# 1_P1_schdoc.net
KiCad netlist of a schematic drawn in Altium Designer
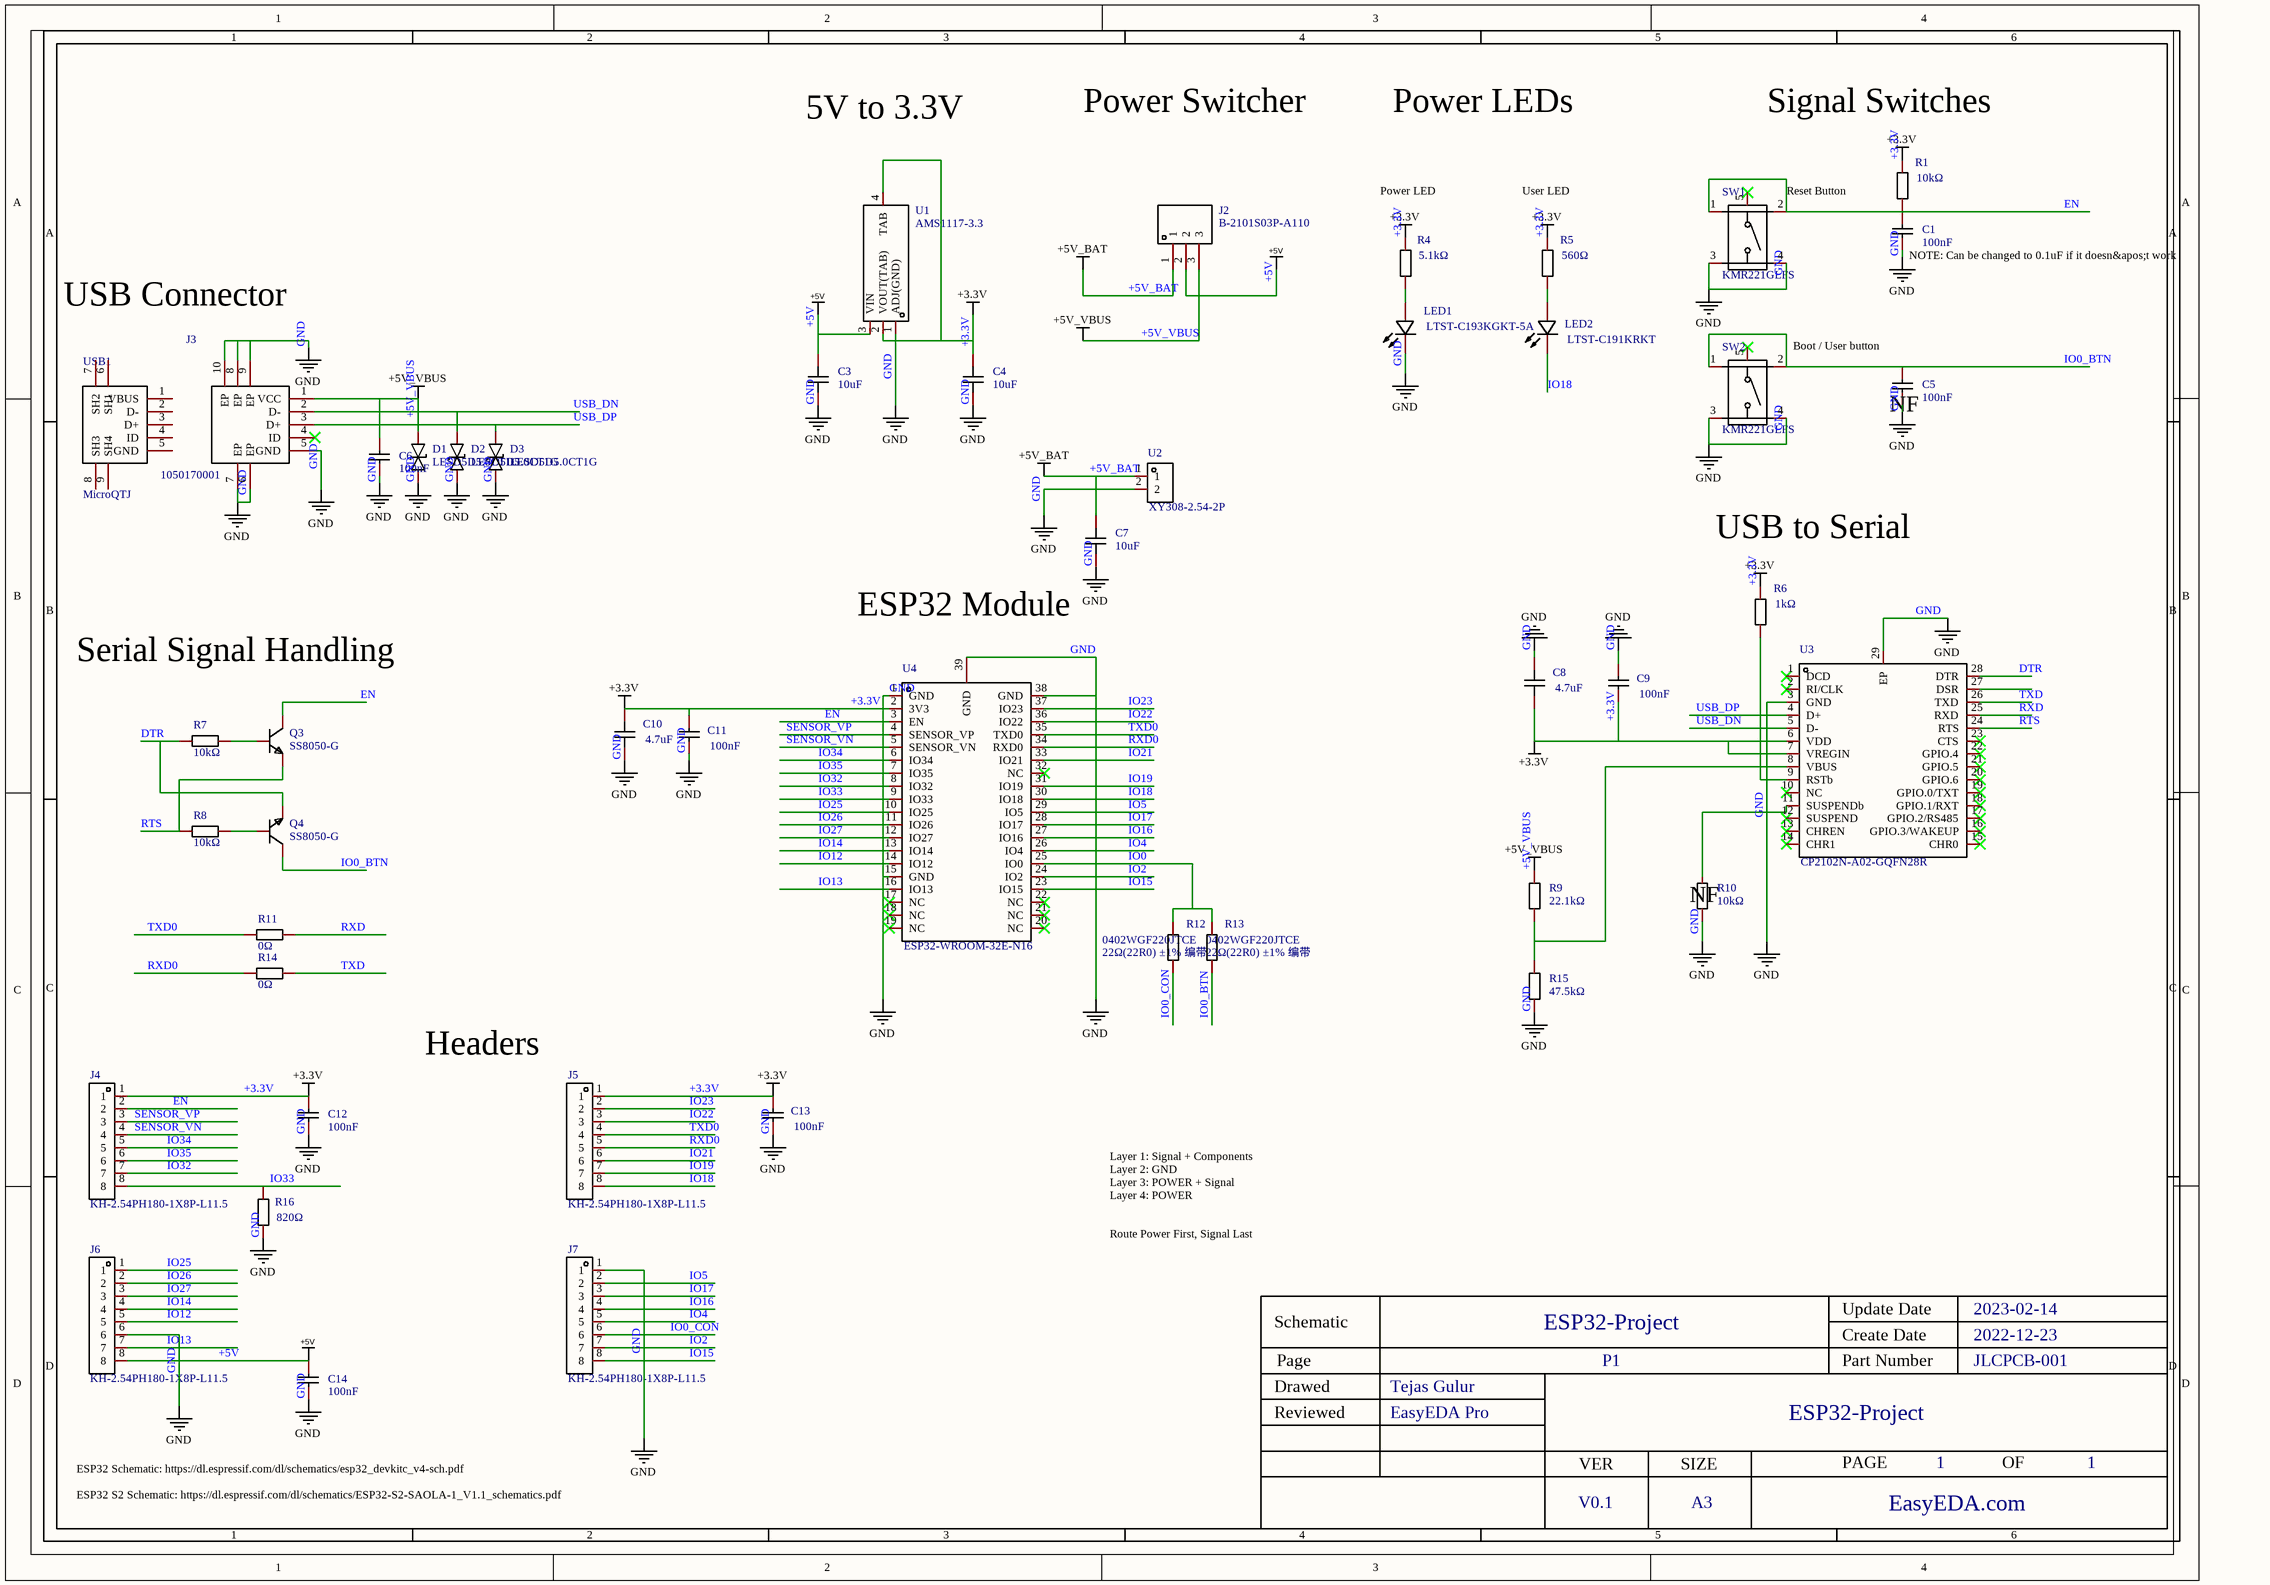
[diagram p0: 1_P1.schdoc.schdoc]

(export (version "E")
  (design (tool "Eeschema 10.0.6"))
  (components
    (comp (ref "C1")
      (value "100nF")
      (fields
        (field (name "NAME") "100nF")
        (field (name "MANUFACTURER") "SAMSUNG(三星)")
        (field (name "MANUFACTURER PART") "CL05B104KO5NNNC")
        (field (name "TOLERANCE") "±10%")
      )
      (libsource (lib "altium-import") (part "root_1_CL05B104KO5NNNC_"))
    )
    (comp (ref "C3")
      (value "10uF")
      (fields
        (field (name "NAME") "10uF")
        (field (name "MANUFACTURER") "SAMSUNG(三星)")
        (field (name "MANUFACTURER PART") "CL05A106MP5NUNC")
        (field (name "TOLERANCE") "±20%")
      )
      (libsource (lib "altium-import") (part "root_1_CL05A106MP5NUNC_C315248_"))
    )
    (comp (ref "C4")
      (value "10uF")
      (fields
        (field (name "NAME") "10uF")
        (field (name "MANUFACTURER") "SAMSUNG(三星)")
        (field (name "MANUFACTURER PART") "CL05A106MP5NUNC")
        (field (name "TOLERANCE") "±20%")
      )
      (libsource (lib "altium-import") (part "root_1_CL05A106MP5NUNC_C315248_"))
    )
    (comp (ref "C5")
      (value "100nF")
      (fields
        (field (name "NAME") "100nF")
        (field (name "MANUFACTURER") "SAMSUNG(三星)")
        (field (name "MANUFACTURER PART") "CL05B104KO5NNNC")
        (field (name "TOLERANCE") "±10%")
      )
      (libsource (lib "altium-import") (part "root_1_CL05B104KO5NNNC_"))
    )
    (comp (ref "C6")
      (value "100nF")
      (fields
        (field (name "NAME") "100nF")
        (field (name "MANUFACTURER") "SAMSUNG(三星)")
        (field (name "MANUFACTURER PART") "CL05B104KO5NNNC")
        (field (name "TOLERANCE") "±10%")
      )
      (libsource (lib "altium-import") (part "root_1_CL05B104KO5NNNC_"))
    )
    (comp (ref "C7")
      (value "10uF")
      (fields
        (field (name "NAME") "10uF")
        (field (name "MANUFACTURER") "SAMSUNG(三星)")
        (field (name "MANUFACTURER PART") "CL05A106MP5NUNC")
        (field (name "TOLERANCE") "±20%")
      )
      (libsource (lib "altium-import") (part "root_1_CL05A106MP5NUNC_C315248_"))
    )
    (comp (ref "C8")
      (value "4.7uF")
      (fields
        (field (name "NAME") "4.7uF")
        (field (name "MANUFACTURER") "SAMSUNG(三星)")
        (field (name "MANUFACTURER PART") "CL05A475KP5NRNC")
        (field (name "TOLERANCE") "±10%")
      )
      (libsource (lib "altium-import") (part "root_0_CL05A475KP5NRNC_"))
    )
    (comp (ref "C9")
      (value "100nF")
      (fields
        (field (name "NAME") "100nF")
        (field (name "MANUFACTURER") "SAMSUNG(三星)")
        (field (name "MANUFACTURER PART") "CL05B104KO5NNNC")
        (field (name "TOLERANCE") "±10%")
      )
      (libsource (lib "altium-import") (part "root_1_CL05B104KO5NNNC_"))
    )
    (comp (ref "C10")
      (value "4.7uF")
      (fields
        (field (name "NAME") "4.7uF")
        (field (name "MANUFACTURER") "SAMSUNG(三星)")
        (field (name "MANUFACTURER PART") "CL05A475KP5NRNC")
        (field (name "TOLERANCE") "±10%")
      )
      (libsource (lib "altium-import") (part "root_0_CL05A475KP5NRNC_"))
    )
    (comp (ref "C11")
      (value "100nF")
      (fields
        (field (name "NAME") "100nF")
        (field (name "MANUFACTURER") "SAMSUNG(三星)")
        (field (name "MANUFACTURER PART") "CL05B104KO5NNNC")
        (field (name "TOLERANCE") "±10%")
      )
      (libsource (lib "altium-import") (part "root_1_CL05B104KO5NNNC_"))
    )
    (comp (ref "C12")
      (value "100nF")
      (fields
        (field (name "NAME") "100nF")
        (field (name "MANUFACTURER") "SAMSUNG(三星)")
        (field (name "MANUFACTURER PART") "CL05B104KO5NNNC")
        (field (name "TOLERANCE") "±10%")
      )
      (libsource (lib "altium-import") (part "root_1_CL05B104KO5NNNC_"))
    )
    (comp (ref "C13")
      (value "100nF")
      (fields
        (field (name "NAME") "100nF")
        (field (name "MANUFACTURER") "SAMSUNG(三星)")
        (field (name "MANUFACTURER PART") "CL05B104KO5NNNC")
        (field (name "TOLERANCE") "±10%")
      )
      (libsource (lib "altium-import") (part "root_1_CL05B104KO5NNNC_"))
    )
    (comp (ref "C14")
      (value "100nF")
      (fields
        (field (name "NAME") "100nF")
        (field (name "MANUFACTURER") "SAMSUNG(三星)")
        (field (name "MANUFACTURER PART") "CL05B104KO5NNNC")
        (field (name "TOLERANCE") "±10%")
      )
      (libsource (lib "altium-import") (part "root_1_CL05B104KO5NNNC_"))
    )
    (comp (ref "D1")
      (value "LESD5D5.0CT1G")
      (fields (field (name "NAME") "LESD5D5.0CT1G") (field (name "MANUFACTURER") "LRC(乐山无线电)"))
      (libsource (lib "altium-import") (part "root_1_LESD5D5.0CT1G_"))
    )
    (comp (ref "D2")
      (value "LESD5D5.0CT1G")
      (fields (field (name "NAME") "LESD5D5.0CT1G") (field (name "MANUFACTURER") "LRC(乐山无线电)"))
      (libsource (lib "altium-import") (part "root_1_LESD5D5.0CT1G_"))
    )
    (comp (ref "D3")
      (value "LESD5D5.0CT1G")
      (fields (field (name "NAME") "LESD5D5.0CT1G") (field (name "MANUFACTURER") "LRC(乐山无线电)"))
      (libsource (lib "altium-import") (part "root_1_LESD5D5.0CT1G_"))
    )
    (comp (ref "J2")
      (value "B-2101S03P-A110")
      (fields (field (name "NAME") "B-2101S03P-A110") (field (name "MANUFACTURER") "Ckmtw(灿科盟)"))
      (libsource (lib "altium-import") (part "root_1_B-2101S03P-A110_"))
    )
    (comp (ref "J3")
      (value "1050170001")
      (fields (field (name "NAME") "1050170001") (field (name "MANUFACTURER") "MOLEX"))
      (libsource (lib "altium-import") (part "root_0_mirrored_1050170001_"))
    )
    (comp (ref "J4")
      (value "KH-2.54PH180-1X8P-L11.5")
      (fields (field (name "NAME") "KH-2.54PH180-1X8P-L11.5") (field (name "MANUFACTURER") "kinghelm(金航标)"))
      (libsource (lib "altium-import") (part "root_0_mirrored_KH-2.54PH180-1X8P-L11.5_"))
    )
    (comp (ref "J5")
      (value "KH-2.54PH180-1X8P-L11.5")
      (fields (field (name "NAME") "KH-2.54PH180-1X8P-L11.5") (field (name "MANUFACTURER") "kinghelm(金航标)"))
      (libsource (lib "altium-import") (part "root_0_mirrored_KH-2.54PH180-1X8P-L11.5_"))
    )
    (comp (ref "J6")
      (value "KH-2.54PH180-1X8P-L11.5")
      (fields (field (name "NAME") "KH-2.54PH180-1X8P-L11.5") (field (name "MANUFACTURER") "kinghelm(金航标)"))
      (libsource (lib "altium-import") (part "root_0_mirrored_KH-2.54PH180-1X8P-L11.5_"))
    )
    (comp (ref "J7")
      (value "KH-2.54PH180-1X8P-L11.5")
      (fields (field (name "NAME") "KH-2.54PH180-1X8P-L11.5") (field (name "MANUFACTURER") "kinghelm(金航标)"))
      (libsource (lib "altium-import") (part "root_0_mirrored_KH-2.54PH180-1X8P-L11.5_"))
    )
    (comp (ref "LED1")
      (value "LTST-C193KGKT-5A")
      (fields (field (name "NAME") "LTST-C193KGKT-5A") (field (name "MANUFACTURER") "LITEON(光宝)"))
      (libsource (lib "altium-import") (part "root_1_LTST-C193KGKT-5A_"))
    )
    (comp (ref "LED2")
      (value "LTST-C191KRKT")
      (fields (field (name "NAME") "LTST-C191KRKT") (field (name "MANUFACTURER") "LITEON(光宝)"))
      (libsource (lib "altium-import") (part "root_1_LTST-C191KRKT_"))
    )
    (comp (ref "Q3")
      (value "SS8050-G")
      (fields (field (name "NAME") "SS8050-G") (field (name "MANUFACTURER") "CJ(江苏长电/长晶)"))
      (libsource (lib "altium-import") (part "root_0_SS8050-G_"))
    )
    (comp (ref "Q4")
      (value "SS8050-G")
      (fields (field (name "NAME") "SS8050-G") (field (name "MANUFACTURER") "CJ(江苏长电/长晶)"))
      (libsource (lib "altium-import") (part "root_2_mirrored_SS8050-G_"))
    )
    (comp (ref "R1")
      (value "10kΩ")
      (fields
        (field (name "NAME") "10kΩ")
        (field (name "MANUFACTURER") "UNI-ROYAL(厚声)")
        (field (name "MANUFACTURER PART") "0402WGF1002TCE")
        (field (name "TOLERANCE") "±1%")
      )
      (libsource (lib "altium-import") (part "root_1_0402WGF1002TCE_"))
    )
    (comp (ref "R4")
      (value "5.1kΩ")
      (fields
        (field (name "NAME") "5.1kΩ")
        (field (name "MANUFACTURER") "UNI-ROYAL(厚声)")
        (field (name "MANUFACTURER PART") "0402WGJ0512TCE")
        (field (name "TOLERANCE") "±5%")
      )
      (libsource (lib "altium-import") (part "root_1_0402WGJ0512TCE_"))
    )
    (comp (ref "R5")
      (value "560Ω")
      (fields
        (field (name "NAME") "560Ω")
        (field (name "MANUFACTURER") "UNI-ROYAL(厚声)")
        (field (name "MANUFACTURER PART") "0402WGJ0561TCE")
        (field (name "TOLERANCE") "±5%")
      )
      (libsource (lib "altium-import") (part "root_1_0402WGJ0561TCE_"))
    )
    (comp (ref "R6")
      (value "1kΩ")
      (fields
        (field (name "NAME") "1kΩ")
        (field (name "MANUFACTURER") "UNI-ROYAL(厚声)")
        (field (name "MANUFACTURER PART") "0402WGF1001TCE")
        (field (name "TOLERANCE") "±1%")
      )
      (libsource (lib "altium-import") (part "root_1_0402WGF1001TCE_"))
    )
    (comp (ref "R7")
      (value "10kΩ")
      (fields
        (field (name "NAME") "10kΩ")
        (field (name "MANUFACTURER") "UNI-ROYAL(厚声)")
        (field (name "MANUFACTURER PART") "0402WGF1002TCE")
        (field (name "TOLERANCE") "±1%")
      )
      (libsource (lib "altium-import") (part "root_0_0402WGF1002TCE_"))
    )
    (comp (ref "R8")
      (value "10kΩ")
      (fields
        (field (name "NAME") "10kΩ")
        (field (name "MANUFACTURER") "UNI-ROYAL(厚声)")
        (field (name "MANUFACTURER PART") "0402WGF1002TCE")
        (field (name "TOLERANCE") "±1%")
      )
      (libsource (lib "altium-import") (part "root_0_0402WGF1002TCE_"))
    )
    (comp (ref "R9")
      (value "22.1kΩ")
      (fields
        (field (name "NAME") "22.1kΩ")
        (field (name "MANUFACTURER") "UNI-ROYAL(厚声)")
        (field (name "MANUFACTURER PART") "0402WGF2212TCE")
        (field (name "TOLERANCE") "±1%")
      )
      (libsource (lib "altium-import") (part "root_3_0402WGF2212TCE_"))
    )
    (comp (ref "R10")
      (value "10kΩ")
      (fields
        (field (name "NAME") "10kΩ")
        (field (name "MANUFACTURER") "UNI-ROYAL(厚声)")
        (field (name "MANUFACTURER PART") "0402WGF1002TCE")
        (field (name "TOLERANCE") "±1%")
      )
      (libsource (lib "altium-import") (part "root_3_0402WGF1002TCE_"))
    )
    (comp (ref "R11")
      (value "0Ω")
      (fields
        (field (name "NAME") "0Ω")
        (field (name "MANUFACTURER") "UNI-ROYAL(厚声)")
        (field (name "MANUFACTURER PART") "0402WGF0000TCE")
        (field (name "TOLERANCE") "±1%")
      )
      (libsource (lib "altium-import") (part "root_0_0402WGF0000TCE_"))
    )
    (comp (ref "R12")
      (value "0402WGF220JTCE")
      (fields
        (field (name "NAME") "0402WGF220JTCE")
        (field (name "LCSC PART NAME") "22Ω(22R0) ±1% 编带")
        (field (name "MANUFACTURER") "UNI-ROYAL(厚声)")
      )
      (libsource (lib "altium-import") (part "root_1_0402WGF220JTCE_"))
    )
    (comp (ref "R13")
      (value "0402WGF220JTCE")
      (fields
        (field (name "NAME") "0402WGF220JTCE")
        (field (name "LCSC PART NAME") "22Ω(22R0) ±1% 编带")
        (field (name "MANUFACTURER") "UNI-ROYAL(厚声)")
      )
      (libsource (lib "altium-import") (part "root_1_0402WGF220JTCE_"))
    )
    (comp (ref "R14")
      (value "0Ω")
      (fields
        (field (name "NAME") "0Ω")
        (field (name "MANUFACTURER") "UNI-ROYAL(厚声)")
        (field (name "MANUFACTURER PART") "0402WGF0000TCE")
        (field (name "TOLERANCE") "±1%")
      )
      (libsource (lib "altium-import") (part "root_0_0402WGF0000TCE_"))
    )
    (comp (ref "R15")
      (value "47.5kΩ")
      (fields
        (field (name "NAME") "47.5kΩ")
        (field (name "MANUFACTURER") "UNI-ROYAL(厚声)")
        (field (name "MANUFACTURER PART") "0402WGF4752TCE")
        (field (name "TOLERANCE") "±1%")
      )
      (libsource (lib "altium-import") (part "root_1_0402WGF4752TCE_"))
    )
    (comp (ref "R16")
      (value "820Ω")
      (fields
        (field (name "NAME") "820Ω")
        (field (name "MANUFACTURER") "UNI-ROYAL(厚声)")
        (field (name "MANUFACTURER PART") "0402WGF8200TCE")
        (field (name "TOLERANCE") "±1%")
      )
      (libsource (lib "altium-import") (part "root_1_0402WGF8200TCE_"))
    )
    (comp (ref "SW1")
      (value "KMR221GLFS")
      (fields (field (name "NAME") "KMR221GLFS") (field (name "MANUFACTURER") "C&K"))
      (libsource (lib "altium-import") (part "root_0_KMR221GLFS_"))
    )
    (comp (ref "SW2")
      (value "KMR221GLFS")
      (fields (field (name "NAME") "KMR221GLFS") (field (name "MANUFACTURER") "C&K"))
      (libsource (lib "altium-import") (part "root_0_KMR221GLFS_"))
    )
    (comp (ref "U1")
      (value "AMS1117-3.3")
      (fields (field (name "NAME") "AMS1117-3.3") (field (name "MANUFACTURER") "UMW(广东友台半导体)"))
      (libsource (lib "altium-import") (part "root_1_mirrored_AMS1117-3.3_C347222_"))
    )
    (comp (ref "U2")
      (value "XY308-2.54-2P")
      (fields (field (name "NAME") "XY308-2.54-2P") (field (name "MANUFACTURER") "XINLAIYA(新莱亚)"))
      (libsource (lib "altium-import") (part "root_0_XY308-2.54-2P_"))
    )
    (comp (ref "U3")
      (value "CP2102N-A02-GQFN28R")
      (fields (field (name "NAME") "CP2102N-A02-GQFN28R") (field (name "MANUFACTURER") "SILICON LABS(芯科)"))
      (libsource (lib "altium-import") (part "root_0_CP2102N-A02-GQFN28R_"))
    )
    (comp (ref "U4")
      (value "ESP32-WROOM-32E-N16")
      (fields (field (name "NAME") "ESP32-WROOM-32E-N16") (field (name "MANUFACTURER") "ESPRESSIF(乐鑫)"))
      (libsource (lib "altium-import") (part "root_0_ESP32-WROOM-32E-N16_C701343_"))
    )
    (comp (ref "USB1")
      (value "MicroQTJ")
      (fields (field (name "NAME") "MicroQTJ") (field (name "MANUFACTURER") "SHOU HAN(首韩)"))
      (libsource (lib "altium-import") (part "root_0_MicroQTJ_"))
    )
  )
  (nets
    (net (code "1") (name "+3.3V") (class "Default")
      (node (ref "C10") (pin "2") (pinfunction "2_2") (pintype "passive"))
      (node (ref "C11") (pin "2") (pinfunction "2_2") (pintype "passive"))
      (node (ref "C12") (pin "2") (pinfunction "2_2") (pintype "passive"))
      (node (ref "C13") (pin "2") (pinfunction "2_2") (pintype "passive"))
      (node (ref "C4") (pin "2") (pinfunction "2_2") (pintype "passive"))
      (node (ref "C8") (pin "1") (pinfunction "1_1") (pintype "passive"))
      (node (ref "C9") (pin "1") (pinfunction "1_1") (pintype "passive"))
      (node (ref "J4") (pin "1") (pinfunction "1_1") (pintype "passive"))
      (node (ref "J5") (pin "1") (pinfunction "1_1") (pintype "passive"))
      (node (ref "R1") (pin "2") (pinfunction "2_2") (pintype "passive"))
      (node (ref "R4") (pin "2") (pinfunction "2_2") (pintype "passive"))
      (node (ref "R5") (pin "2") (pinfunction "2_2") (pintype "passive"))
      (node (ref "R6") (pin "2") (pinfunction "2_2") (pintype "passive"))
      (node (ref "U1") (pin "2") (pinfunction "VOUT(TAB)_2") (pintype "passive"))
      (node (ref "U1") (pin "4") (pinfunction "TAB_4") (pintype "passive"))
      (node (ref "U3") (pin "6") (pinfunction "VDD_6") (pintype "passive"))
      (node (ref "U3") (pin "7") (pinfunction "VREGIN_7") (pintype "passive"))
      (node (ref "U4") (pin "2") (pinfunction "3V3_2") (pintype "passive"))
    )
    (net (code "2") (name "+5V") (class "Default")
      (node (ref "C14") (pin "2") (pinfunction "2_2") (pintype "passive"))
      (node (ref "C3") (pin "2") (pinfunction "2_2") (pintype "passive"))
      (node (ref "J2") (pin "2") (pinfunction "2_2") (pintype "passive"))
      (node (ref "J6") (pin "8") (pinfunction "8_8") (pintype "passive"))
      (node (ref "U1") (pin "3") (pinfunction "VIN_3") (pintype "passive"))
    )
    (net (code "3") (name "+5V_BAT") (class "Default")
      (node (ref "C7") (pin "2") (pinfunction "2_2") (pintype "passive"))
      (node (ref "J2") (pin "1") (pinfunction "1_1") (pintype "passive"))
      (node (ref "U2") (pin "1") (pinfunction "1_1") (pintype "passive"))
    )
    (net (code "4") (name "+5V_VBUS") (class "Default")
      (node (ref "C6") (pin "2") (pinfunction "2_2") (pintype "passive"))
      (node (ref "D1") (pin "2") (pinfunction "2_2") (pintype "passive"))
      (node (ref "J2") (pin "3") (pinfunction "3_3") (pintype "passive"))
      (node (ref "J3") (pin "1") (pinfunction "VCC_1") (pintype "passive"))
      (node (ref "R9") (pin "1") (pinfunction "1_1") (pintype "passive"))
    )
    (net (code "5") (name "/DTR") (class "Default")
      (node (ref "Q4") (pin "2") (pinfunction "E_2") (pintype "passive"))
      (node (ref "R7") (pin "1") (pinfunction "1_1") (pintype "passive"))
      (node (ref "U3") (pin "28") (pinfunction "DTR_28") (pintype "passive"))
    )
    (net (code "6") (name "/EN") (class "Default")
      (node (ref "C1") (pin "2") (pinfunction "2_2") (pintype "passive"))
      (node (ref "J4") (pin "2") (pinfunction "2_2") (pintype "passive"))
      (node (ref "Q3") (pin "3") (pinfunction "C_3") (pintype "passive"))
      (node (ref "R1") (pin "1") (pinfunction "1_1") (pintype "passive"))
      (node (ref "SW1") (pin "1") (pinfunction "1_1") (pintype "passive"))
      (node (ref "SW1") (pin "2") (pinfunction "2_2") (pintype "passive"))
      (node (ref "U4") (pin "3") (pinfunction "EN_3") (pintype "passive"))
    )
    (net (code "7") (name "/IO0") (class "Default")
      (node (ref "R12") (pin "2") (pinfunction "2_2") (pintype "passive"))
      (node (ref "R13") (pin "2") (pinfunction "2_2") (pintype "passive"))
      (node (ref "U4") (pin "25") (pinfunction "IO0_25") (pintype "passive"))
    )
    (net (code "8") (name "/IO0_BTN") (class "Default")
      (node (ref "C5") (pin "2") (pinfunction "2_2") (pintype "passive"))
      (node (ref "Q4") (pin "3") (pinfunction "C_3") (pintype "passive"))
      (node (ref "R13") (pin "1") (pinfunction "1_1") (pintype "passive"))
      (node (ref "SW2") (pin "1") (pinfunction "1_1") (pintype "passive"))
      (node (ref "SW2") (pin "2") (pinfunction "2_2") (pintype "passive"))
    )
    (net (code "9") (name "/IO0_CON") (class "Default")
      (node (ref "J7") (pin "6") (pinfunction "6_6") (pintype "passive"))
      (node (ref "R12") (pin "1") (pinfunction "1_1") (pintype "passive"))
    )
    (net (code "10") (name "/IO2") (class "Default")
      (node (ref "J7") (pin "7") (pinfunction "7_7") (pintype "passive"))
      (node (ref "U4") (pin "24") (pinfunction "IO2_24") (pintype "passive"))
    )
    (net (code "11") (name "/IO4") (class "Default")
      (node (ref "J7") (pin "5") (pinfunction "5_5") (pintype "passive"))
      (node (ref "U4") (pin "26") (pinfunction "IO4_26") (pintype "passive"))
    )
    (net (code "12") (name "/IO5") (class "Default")
      (node (ref "J7") (pin "2") (pinfunction "2_2") (pintype "passive"))
      (node (ref "U4") (pin "29") (pinfunction "IO5_29") (pintype "passive"))
    )
    (net (code "13") (name "/IO12") (class "Default")
      (node (ref "J6") (pin "5") (pinfunction "5_5") (pintype "passive"))
      (node (ref "U4") (pin "14") (pinfunction "IO12_14") (pintype "passive"))
    )
    (net (code "14") (name "/IO13") (class "Default")
      (node (ref "J6") (pin "7") (pinfunction "7_7") (pintype "passive"))
      (node (ref "U4") (pin "16") (pinfunction "IO13_16") (pintype "passive"))
    )
    (net (code "15") (name "/IO14") (class "Default")
      (node (ref "J6") (pin "4") (pinfunction "4_4") (pintype "passive"))
      (node (ref "U4") (pin "13") (pinfunction "IO14_13") (pintype "passive"))
    )
    (net (code "16") (name "/IO15") (class "Default")
      (node (ref "J7") (pin "8") (pinfunction "8_8") (pintype "passive"))
      (node (ref "U4") (pin "23") (pinfunction "IO15_23") (pintype "passive"))
    )
    (net (code "17") (name "/IO16") (class "Default")
      (node (ref "J7") (pin "4") (pinfunction "4_4") (pintype "passive"))
      (node (ref "U4") (pin "27") (pinfunction "IO16_27") (pintype "passive"))
    )
    (net (code "18") (name "/IO17") (class "Default")
      (node (ref "J7") (pin "3") (pinfunction "3_3") (pintype "passive"))
      (node (ref "U4") (pin "28") (pinfunction "IO17_28") (pintype "passive"))
    )
    (net (code "19") (name "/IO18") (class "Default")
      (node (ref "J5") (pin "8") (pinfunction "8_8") (pintype "passive"))
      (node (ref "LED2") (pin "1") (pinfunction "-_1") (pintype "passive"))
      (node (ref "U4") (pin "30") (pinfunction "IO18_30") (pintype "passive"))
    )
    (net (code "20") (name "/IO19") (class "Default")
      (node (ref "J5") (pin "7") (pinfunction "7_7") (pintype "passive"))
      (node (ref "U4") (pin "31") (pinfunction "IO19_31") (pintype "passive"))
    )
    (net (code "21") (name "/IO21") (class "Default")
      (node (ref "J5") (pin "6") (pinfunction "6_6") (pintype "passive"))
      (node (ref "U4") (pin "33") (pinfunction "IO21_33") (pintype "passive"))
    )
    (net (code "22") (name "/IO22") (class "Default")
      (node (ref "J5") (pin "3") (pinfunction "3_3") (pintype "passive"))
      (node (ref "U4") (pin "36") (pinfunction "IO22_36") (pintype "passive"))
    )
    (net (code "23") (name "/IO23") (class "Default")
      (node (ref "J5") (pin "2") (pinfunction "2_2") (pintype "passive"))
      (node (ref "U4") (pin "37") (pinfunction "IO23_37") (pintype "passive"))
    )
    (net (code "24") (name "/IO25") (class "Default")
      (node (ref "J6") (pin "1") (pinfunction "1_1") (pintype "passive"))
      (node (ref "U4") (pin "10") (pinfunction "IO25_10") (pintype "passive"))
    )
    (net (code "25") (name "/IO26") (class "Default")
      (node (ref "J6") (pin "2") (pinfunction "2_2") (pintype "passive"))
      (node (ref "U4") (pin "11") (pinfunction "IO26_11") (pintype "passive"))
    )
    (net (code "26") (name "/IO27") (class "Default")
      (node (ref "J6") (pin "3") (pinfunction "3_3") (pintype "passive"))
      (node (ref "U4") (pin "12") (pinfunction "IO27_12") (pintype "passive"))
    )
    (net (code "27") (name "/IO32") (class "Default")
      (node (ref "J4") (pin "7") (pinfunction "7_7") (pintype "passive"))
      (node (ref "U4") (pin "8") (pinfunction "IO32_8") (pintype "passive"))
    )
    (net (code "28") (name "/IO33") (class "Default")
      (node (ref "J4") (pin "8") (pinfunction "8_8") (pintype "passive"))
      (node (ref "R16") (pin "2") (pinfunction "2_2") (pintype "passive"))
      (node (ref "U4") (pin "9") (pinfunction "IO33_9") (pintype "passive"))
    )
    (net (code "29") (name "/IO34") (class "Default")
      (node (ref "J4") (pin "5") (pinfunction "5_5") (pintype "passive"))
      (node (ref "U4") (pin "6") (pinfunction "IO34_6") (pintype "passive"))
    )
    (net (code "30") (name "/IO35") (class "Default")
      (node (ref "J4") (pin "6") (pinfunction "6_6") (pintype "passive"))
      (node (ref "U4") (pin "7") (pinfunction "IO35_7") (pintype "passive"))
    )
    (net (code "31") (name "/RTS") (class "Default")
      (node (ref "Q3") (pin "2") (pinfunction "E_2") (pintype "passive"))
      (node (ref "R8") (pin "1") (pinfunction "1_1") (pintype "passive"))
      (node (ref "U3") (pin "24") (pinfunction "RTS_24") (pintype "passive"))
    )
    (net (code "32") (name "/RXD") (class "Default")
      (node (ref "R11") (pin "2") (pinfunction "2_2") (pintype "passive"))
      (node (ref "U3") (pin "25") (pinfunction "RXD_25") (pintype "passive"))
    )
    (net (code "33") (name "/RXD0") (class "Default")
      (node (ref "J5") (pin "5") (pinfunction "5_5") (pintype "passive"))
      (node (ref "R14") (pin "1") (pinfunction "1_1") (pintype "passive"))
      (node (ref "U4") (pin "34") (pinfunction "RXD0_34") (pintype "passive"))
    )
    (net (code "34") (name "/SENSOR_VN") (class "Default")
      (node (ref "J4") (pin "4") (pinfunction "4_4") (pintype "passive"))
      (node (ref "U4") (pin "5") (pinfunction "SENSOR_VN_5") (pintype "passive"))
    )
    (net (code "35") (name "/SENSOR_VP") (class "Default")
      (node (ref "J4") (pin "3") (pinfunction "3_3") (pintype "passive"))
      (node (ref "U4") (pin "4") (pinfunction "SENSOR_VP_4") (pintype "passive"))
    )
    (net (code "36") (name "/TXD") (class "Default")
      (node (ref "R14") (pin "2") (pinfunction "2_2") (pintype "passive"))
      (node (ref "U3") (pin "26") (pinfunction "TXD_26") (pintype "passive"))
    )
    (net (code "37") (name "/TXD0") (class "Default")
      (node (ref "J5") (pin "4") (pinfunction "4_4") (pintype "passive"))
      (node (ref "R11") (pin "1") (pinfunction "1_1") (pintype "passive"))
      (node (ref "U4") (pin "35") (pinfunction "TXD0_35") (pintype "passive"))
    )
    (net (code "38") (name "/USB_DN") (class "Default")
      (node (ref "D2") (pin "2") (pinfunction "2_2") (pintype "passive"))
      (node (ref "J3") (pin "2") (pinfunction "D-_2") (pintype "passive"))
      (node (ref "U3") (pin "5") (pinfunction "D-_5") (pintype "passive"))
    )
    (net (code "39") (name "/USB_DP") (class "Default")
      (node (ref "D3") (pin "2") (pinfunction "2_2") (pintype "passive"))
      (node (ref "J3") (pin "3") (pinfunction "D+_3") (pintype "passive"))
      (node (ref "U3") (pin "4") (pinfunction "D+_4") (pintype "passive"))
    )
    (net (code "40") (name "GND") (class "Default")
      (node (ref "C1") (pin "1") (pinfunction "1_1") (pintype "passive"))
      (node (ref "C10") (pin "1") (pinfunction "1_1") (pintype "passive"))
      (node (ref "C11") (pin "1") (pinfunction "1_1") (pintype "passive"))
      (node (ref "C12") (pin "1") (pinfunction "1_1") (pintype "passive"))
      (node (ref "C13") (pin "1") (pinfunction "1_1") (pintype "passive"))
      (node (ref "C14") (pin "1") (pinfunction "1_1") (pintype "passive"))
      (node (ref "C3") (pin "1") (pinfunction "1_1") (pintype "passive"))
      (node (ref "C4") (pin "1") (pinfunction "1_1") (pintype "passive"))
      (node (ref "C5") (pin "1") (pinfunction "1_1") (pintype "passive"))
      (node (ref "C6") (pin "1") (pinfunction "1_1") (pintype "passive"))
      (node (ref "C7") (pin "1") (pinfunction "1_1") (pintype "passive"))
      (node (ref "C8") (pin "2") (pinfunction "2_2") (pintype "passive"))
      (node (ref "C9") (pin "2") (pinfunction "2_2") (pintype "passive"))
      (node (ref "D1") (pin "1") (pinfunction "1_1") (pintype "passive"))
      (node (ref "D2") (pin "1") (pinfunction "1_1") (pintype "passive"))
      (node (ref "D3") (pin "1") (pinfunction "1_1") (pintype "passive"))
      (node (ref "J3") (pin "10") (pinfunction "EP_10") (pintype "passive"))
      (node (ref "J3") (pin "5") (pinfunction "GND_5") (pintype "passive"))
      (node (ref "J3") (pin "6") (pinfunction "EP_6") (pintype "passive"))
      (node (ref "J3") (pin "7") (pinfunction "EP_7") (pintype "passive"))
      (node (ref "J3") (pin "8") (pinfunction "EP_8") (pintype "passive"))
      (node (ref "J3") (pin "9") (pinfunction "EP_9") (pintype "passive"))
      (node (ref "J6") (pin "6") (pinfunction "6_6") (pintype "passive"))
      (node (ref "J7") (pin "1") (pinfunction "1_1") (pintype "passive"))
      (node (ref "LED1") (pin "1") (pinfunction "-_1") (pintype "passive"))
      (node (ref "R10") (pin "2") (pinfunction "2_2") (pintype "passive"))
      (node (ref "R15") (pin "1") (pinfunction "1_1") (pintype "passive"))
      (node (ref "R16") (pin "1") (pinfunction "1_1") (pintype "passive"))
      (node (ref "SW1") (pin "3") (pinfunction "3_3") (pintype "passive"))
      (node (ref "SW1") (pin "4") (pinfunction "4_4") (pintype "passive"))
      (node (ref "SW2") (pin "3") (pinfunction "3_3") (pintype "passive"))
      (node (ref "SW2") (pin "4") (pinfunction "4_4") (pintype "passive"))
      (node (ref "U1") (pin "1") (pinfunction "ADJ(GND)_1") (pintype "passive"))
      (node (ref "U2") (pin "2") (pinfunction "2_2") (pintype "passive"))
      (node (ref "U3") (pin "29") (pinfunction "EP_29") (pintype "passive"))
      (node (ref "U3") (pin "3") (pinfunction "GND_3") (pintype "passive"))
      (node (ref "U4") (pin "1") (pinfunction "GND_1") (pintype "passive"))
      (node (ref "U4") (pin "15") (pinfunction "GND_15") (pintype "passive"))
      (node (ref "U4") (pin "38") (pinfunction "GND_38") (pintype "passive"))
      (node (ref "U4") (pin "39") (pinfunction "GND_39") (pintype "passive"))
    )
    (net (code "41") (name "Net-(LED1-+)") (class "Default")
      (node (ref "LED1") (pin "2") (pinfunction "+_2") (pintype "passive"))
      (node (ref "R4") (pin "1") (pinfunction "1_1") (pintype "passive"))
    )
    (net (code "42") (name "Net-(LED2-+)") (class "Default")
      (node (ref "LED2") (pin "2") (pinfunction "+_2") (pintype "passive"))
      (node (ref "R5") (pin "1") (pinfunction "1_1") (pintype "passive"))
    )
    (net (code "43") (name "Net-(Q3-B)") (class "Default")
      (node (ref "Q3") (pin "1") (pinfunction "B_1") (pintype "passive"))
      (node (ref "R7") (pin "2") (pinfunction "2_2") (pintype "passive"))
    )
    (net (code "44") (name "Net-(Q4-B)") (class "Default")
      (node (ref "Q4") (pin "1") (pinfunction "B_1") (pintype "passive"))
      (node (ref "R8") (pin "2") (pinfunction "2_2") (pintype "passive"))
    )
    (net (code "45") (name "Net-(U3-RSTb)") (class "Default")
      (node (ref "R6") (pin "1") (pinfunction "1_1") (pintype "passive"))
      (node (ref "U3") (pin "9") (pinfunction "RSTb_9") (pintype "passive"))
    )
    (net (code "46") (name "Net-(U3-SUSPENDb)") (class "Default")
      (node (ref "R10") (pin "1") (pinfunction "1_1") (pintype "passive"))
      (node (ref "U3") (pin "11") (pinfunction "SUSPENDb_11") (pintype "passive"))
    )
    (net (code "47") (name "Net-(U3-VBUS)") (class "Default")
      (node (ref "R15") (pin "2") (pinfunction "2_2") (pintype "passive"))
      (node (ref "R9") (pin "2") (pinfunction "2_2") (pintype "passive"))
      (node (ref "U3") (pin "8") (pinfunction "VBUS_8") (pintype "passive"))
    )
    (net (code "48") (name "unconnected-(J3-ID-Pad4)") (class "Default")
      (node (ref "J3") (pin "4") (pinfunction "ID_4") (pintype "passive+no_connect"))
    )
    (net (code "49") (name "unconnected-(SW1-Pad5)") (class "Default")
      (node (ref "SW1") (pin "5") (pinfunction "5_5") (pintype "passive+no_connect"))
    )
    (net (code "50") (name "unconnected-(SW2-Pad5)") (class "Default")
      (node (ref "SW2") (pin "5") (pinfunction "5_5") (pintype "passive+no_connect"))
    )
    (net (code "51") (name "unconnected-(U3-CHR0-Pad15)") (class "Default")
      (node (ref "U3") (pin "15") (pinfunction "CHR0_15") (pintype "passive+no_connect"))
    )
    (net (code "52") (name "unconnected-(U3-CHR1-Pad14)") (class "Default")
      (node (ref "U3") (pin "14") (pinfunction "CHR1_14") (pintype "passive+no_connect"))
    )
    (net (code "53") (name "unconnected-(U3-CHREN-Pad13)") (class "Default")
      (node (ref "U3") (pin "13") (pinfunction "CHREN_13") (pintype "passive+no_connect"))
    )
    (net (code "54") (name "unconnected-(U3-CTS-Pad23)") (class "Default")
      (node (ref "U3") (pin "23") (pinfunction "CTS_23") (pintype "passive+no_connect"))
    )
    (net (code "55") (name "unconnected-(U3-DCD-Pad1)") (class "Default")
      (node (ref "U3") (pin "1") (pinfunction "DCD_1") (pintype "passive+no_connect"))
    )
    (net (code "56") (name "unconnected-(U3-DSR-Pad27)") (class "Default")
      (node (ref "U3") (pin "27") (pinfunction "DSR_27") (pintype "passive"))
    )
    (net (code "57") (name "unconnected-(U3-GPIO.0{slash}TXT-Pad19)") (class "Default")
      (node (ref "U3") (pin "19") (pinfunction "GPIO.0/TXT_19") (pintype "passive+no_connect"))
    )
    (net (code "58") (name "unconnected-(U3-GPIO.1{slash}RXT-Pad18)") (class "Default")
      (node (ref "U3") (pin "18") (pinfunction "GPIO.1/RXT_18") (pintype "passive+no_connect"))
    )
    (net (code "59") (name "unconnected-(U3-GPIO.2{slash}RS485-Pad17)") (class "Default")
      (node (ref "U3") (pin "17") (pinfunction "GPIO.2/RS485_17") (pintype "passive+no_connect"))
    )
    (net (code "60") (name "unconnected-(U3-GPIO.3{slash}WAKEUP-Pad16)") (class "Default")
      (node (ref "U3") (pin "16") (pinfunction "GPIO.3/WAKEUP_16") (pintype "passive+no_connect"))
    )
    (net (code "61") (name "unconnected-(U3-GPIO.4-Pad22)") (class "Default")
      (node (ref "U3") (pin "22") (pinfunction "GPIO.4_22") (pintype "passive+no_connect"))
    )
    (net (code "62") (name "unconnected-(U3-GPIO.5-Pad21)") (class "Default")
      (node (ref "U3") (pin "21") (pinfunction "GPIO.5_21") (pintype "passive+no_connect"))
    )
    (net (code "63") (name "unconnected-(U3-GPIO.6-Pad20)") (class "Default")
      (node (ref "U3") (pin "20") (pinfunction "GPIO.6_20") (pintype "passive+no_connect"))
    )
    (net (code "64") (name "unconnected-(U3-NC-Pad10)") (class "Default")
      (node (ref "U3") (pin "10") (pinfunction "NC_10") (pintype "passive+no_connect"))
    )
    (net (code "65") (name "unconnected-(U3-RI{slash}CLK-Pad2)") (class "Default")
      (node (ref "U3") (pin "2") (pinfunction "RI/CLK_2") (pintype "passive+no_connect"))
    )
    (net (code "66") (name "unconnected-(U3-SUSPEND-Pad12)") (class "Default")
      (node (ref "U3") (pin "12") (pinfunction "SUSPEND_12") (pintype "passive+no_connect"))
    )
    (net (code "67") (name "unconnected-(U4-NC-Pad17)") (class "Default")
      (node (ref "U4") (pin "17") (pinfunction "NC_17") (pintype "passive+no_connect"))
    )
    (net (code "68") (name "unconnected-(U4-NC-Pad18)") (class "Default")
      (node (ref "U4") (pin "18") (pinfunction "NC_18") (pintype "passive+no_connect"))
    )
    (net (code "69") (name "unconnected-(U4-NC-Pad19)") (class "Default")
      (node (ref "U4") (pin "19") (pinfunction "NC_19") (pintype "passive+no_connect"))
    )
    (net (code "70") (name "unconnected-(U4-NC-Pad20)") (class "Default")
      (node (ref "U4") (pin "20") (pinfunction "NC_20") (pintype "passive+no_connect"))
    )
    (net (code "71") (name "unconnected-(U4-NC-Pad21)") (class "Default")
      (node (ref "U4") (pin "21") (pinfunction "NC_21") (pintype "passive+no_connect"))
    )
    (net (code "72") (name "unconnected-(U4-NC-Pad22)") (class "Default")
      (node (ref "U4") (pin "22") (pinfunction "NC_22") (pintype "passive+no_connect"))
    )
    (net (code "73") (name "unconnected-(U4-NC-Pad32)") (class "Default")
      (node (ref "U4") (pin "32") (pinfunction "NC_32") (pintype "passive+no_connect"))
    )
    (net (code "74") (name "unconnected-(USB1-D+-Pad3)") (class "Default")
      (node (ref "USB1") (pin "3") (pinfunction "D+_3") (pintype "passive"))
    )
    (net (code "75") (name "unconnected-(USB1-D--Pad2)") (class "Default")
      (node (ref "USB1") (pin "2") (pinfunction "D-_2") (pintype "passive"))
    )
    (net (code "76") (name "unconnected-(USB1-GND-Pad5)") (class "Default")
      (node (ref "USB1") (pin "5") (pinfunction "GND_5") (pintype "passive"))
    )
    (net (code "77") (name "unconnected-(USB1-ID-Pad4)") (class "Default")
      (node (ref "USB1") (pin "4") (pinfunction "ID_4") (pintype "passive"))
    )
    (net (code "78") (name "unconnected-(USB1-SH1-Pad6)") (class "Default")
      (node (ref "USB1") (pin "6") (pinfunction "SH1_6") (pintype "passive"))
    )
    (net (code "79") (name "unconnected-(USB1-SH2-Pad7)") (class "Default")
      (node (ref "USB1") (pin "7") (pinfunction "SH2_7") (pintype "passive"))
    )
    (net (code "80") (name "unconnected-(USB1-SH3-Pad8)") (class "Default")
      (node (ref "USB1") (pin "8") (pinfunction "SH3_8") (pintype "passive"))
    )
    (net (code "81") (name "unconnected-(USB1-SH4-Pad9)") (class "Default")
      (node (ref "USB1") (pin "9") (pinfunction "SH4_9") (pintype "passive"))
    )
    (net (code "82") (name "unconnected-(USB1-VBUS-Pad1)") (class "Default")
      (node (ref "USB1") (pin "1") (pinfunction "VBUS_1") (pintype "passive"))
    )
  )
)
